# rp-schield-vias.net
KiCad netlist of a schematic drawn in EAGLE
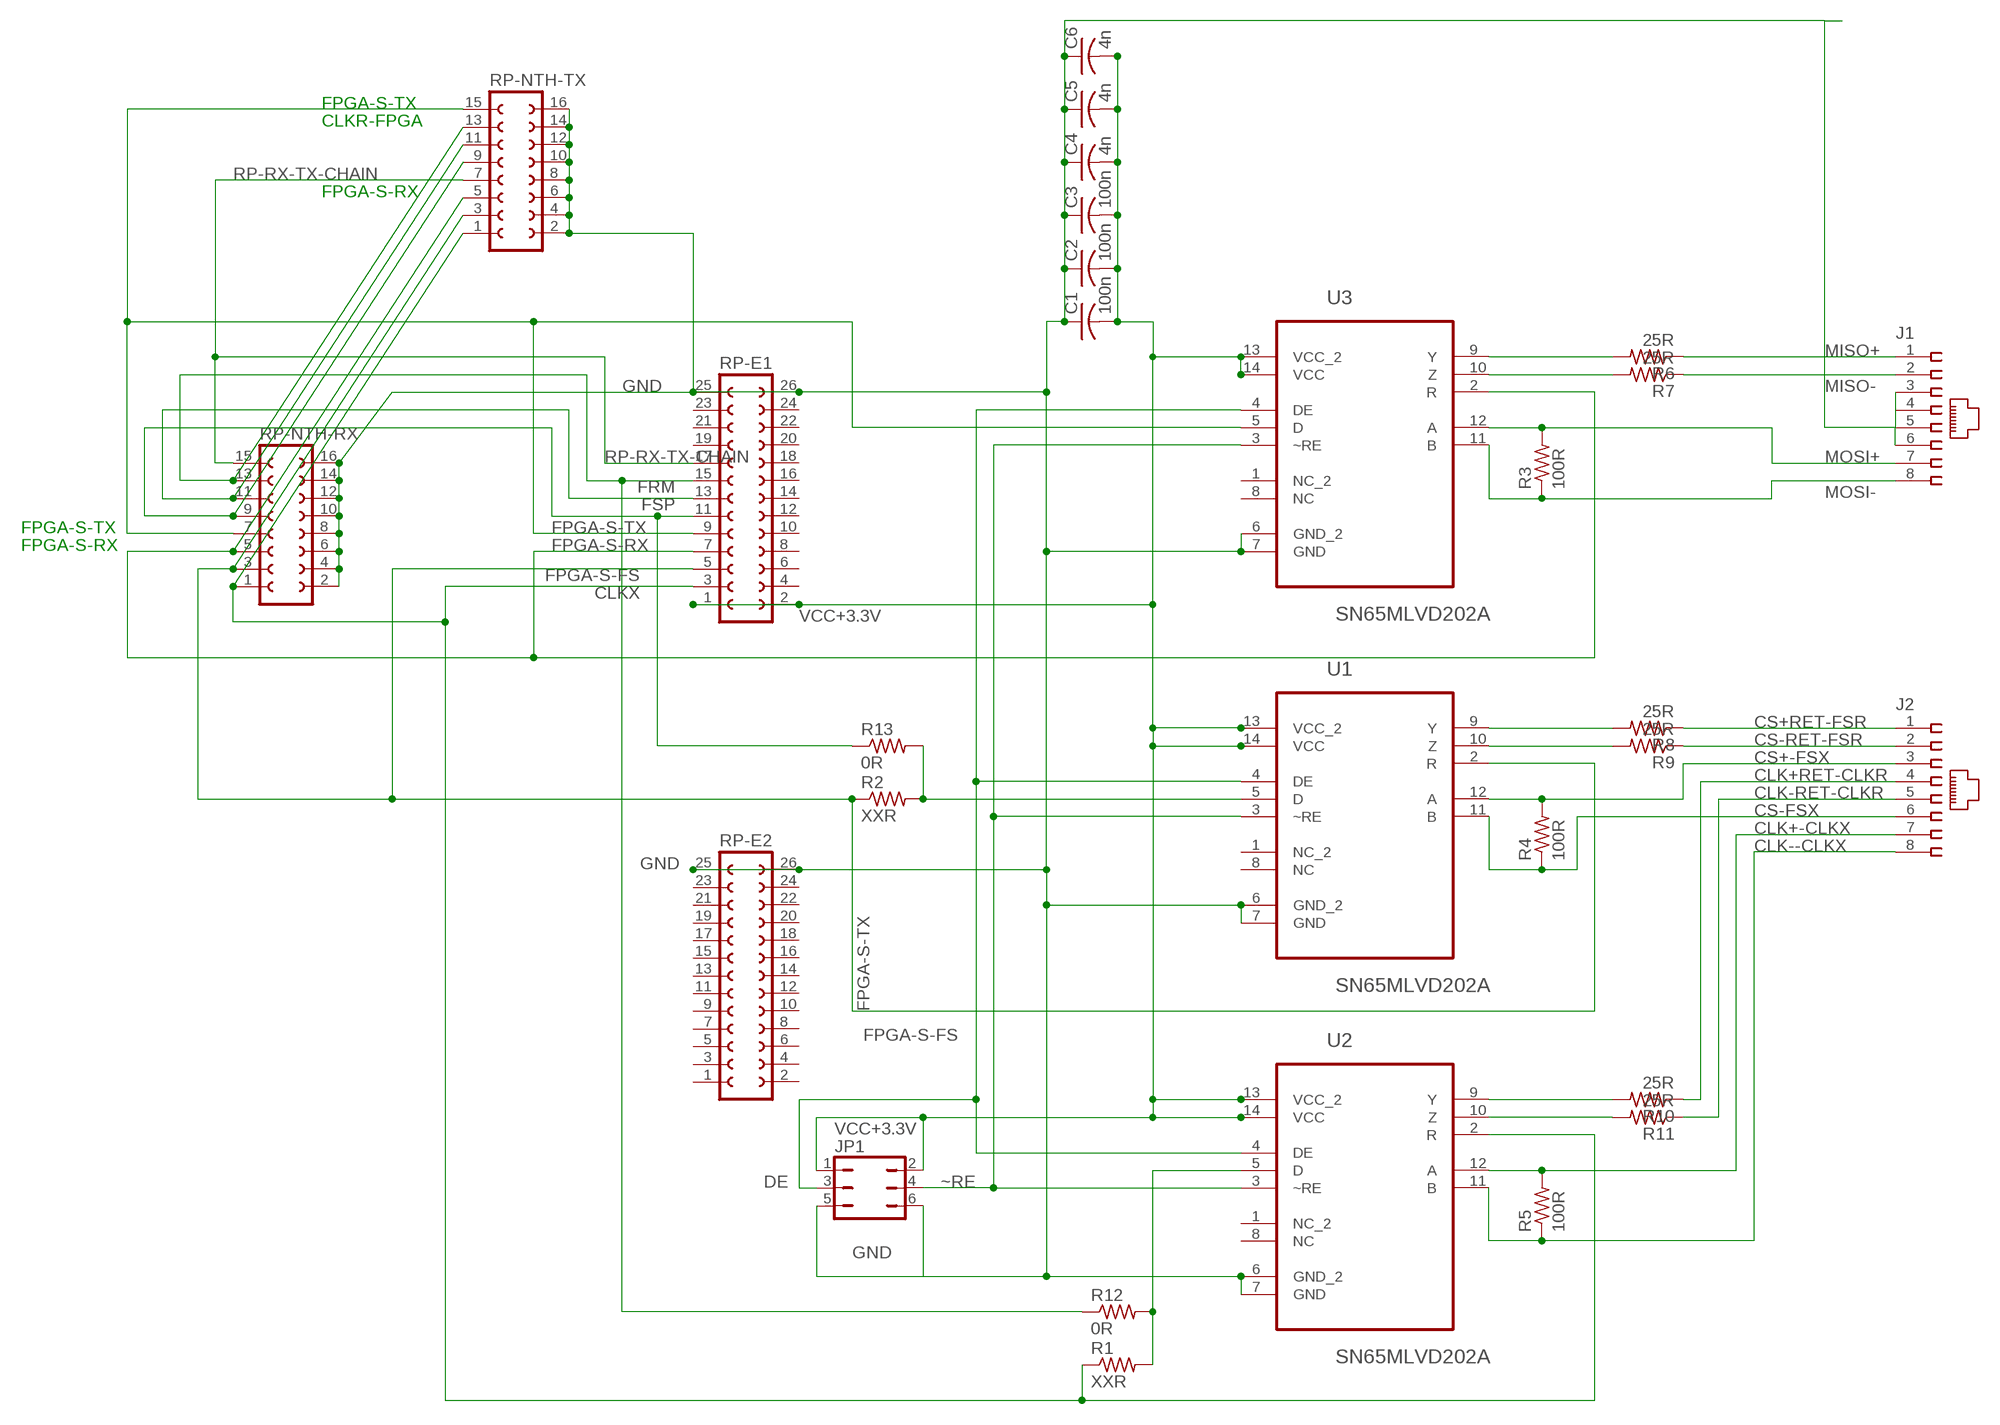
[diagram p0: schematic, sheet 1]

(export (version "E")
  (design (tool "Eeschema 10.0.6"))
  (components
    (comp (ref "C1")
      (value "100n")
      (footprint "eagle-import:C0805")
      (libsource (lib "eagle-import") (part "C-USC0805"))
    )
    (comp (ref "C2")
      (value "100n")
      (footprint "eagle-import:C0805")
      (libsource (lib "eagle-import") (part "C-USC0805"))
    )
    (comp (ref "C3")
      (value "100n")
      (footprint "eagle-import:C0805")
      (libsource (lib "eagle-import") (part "C-USC0805"))
    )
    (comp (ref "C4")
      (value "4n")
      (footprint "eagle-import:C0805")
      (libsource (lib "eagle-import") (part "C-USC0805"))
    )
    (comp (ref "C5")
      (value "4n")
      (footprint "eagle-import:C0805")
      (libsource (lib "eagle-import") (part "C-USC0805"))
    )
    (comp (ref "C6")
      (value "4n")
      (footprint "eagle-import:C0805")
      (libsource (lib "eagle-import") (part "C-USC0805"))
    )
    (comp (ref "J1")
      (value "557785-1-SHIELD")
      (footprint "eagle-import:557785-1")
      (libsource (lib "eagle-import") (part "557785-1-SHIELD"))
    )
    (comp (ref "J2")
      (value "557785-1-SHIELD")
      (footprint "eagle-import:557785-1")
      (libsource (lib "eagle-import") (part "557785-1-SHIELD"))
    )
    (comp (ref "JP1")
      (value "JP3Q")
      (footprint "eagle-import:JP3Q")
      (libsource (lib "eagle-import") (part "JP3Q"))
    )
    (comp (ref "R1")
      (value "XXR")
      (footprint "eagle-import:M1206")
      (libsource (lib "eagle-import") (part "R-US_M1206"))
    )
    (comp (ref "R2")
      (value "XXR")
      (footprint "eagle-import:M1206")
      (libsource (lib "eagle-import") (part "R-US_M1206"))
    )
    (comp (ref "R3")
      (value "100R")
      (footprint "eagle-import:R0402")
      (libsource (lib "eagle-import") (part "R-US_R0402"))
    )
    (comp (ref "R4")
      (value "100R")
      (footprint "eagle-import:R0402")
      (libsource (lib "eagle-import") (part "R-US_R0402"))
    )
    (comp (ref "R5")
      (value "100R")
      (footprint "eagle-import:R0402")
      (libsource (lib "eagle-import") (part "R-US_R0402"))
    )
    (comp (ref "R6")
      (value "25R")
      (footprint "eagle-import:R0402")
      (libsource (lib "eagle-import") (part "R-US_R0402"))
    )
    (comp (ref "R7")
      (value "25R")
      (footprint "eagle-import:R0402")
      (libsource (lib "eagle-import") (part "R-US_R0402"))
    )
    (comp (ref "R8")
      (value "25R")
      (footprint "eagle-import:R0402")
      (libsource (lib "eagle-import") (part "R-US_R0402"))
    )
    (comp (ref "R9")
      (value "25R")
      (footprint "eagle-import:R0402")
      (libsource (lib "eagle-import") (part "R-US_R0402"))
    )
    (comp (ref "R10")
      (value "25R")
      (footprint "eagle-import:R0402")
      (libsource (lib "eagle-import") (part "R-US_R0402"))
    )
    (comp (ref "R11")
      (value "25R")
      (footprint "eagle-import:R0402")
      (libsource (lib "eagle-import") (part "R-US_R0402"))
    )
    (comp (ref "R12")
      (value "0R")
      (footprint "eagle-import:M1206")
      (libsource (lib "eagle-import") (part "R-US_M1206"))
    )
    (comp (ref "R13")
      (value "0R")
      (footprint "eagle-import:M1206")
      (libsource (lib "eagle-import") (part "R-US_M1206"))
    )
    (comp (ref "RP-E1")
      (value "FE13-2")
      (footprint "eagle-import:FE13-2")
      (libsource (lib "eagle-import") (part "FE13-2"))
    )
    (comp (ref "RP-E2")
      (value "FE13-2")
      (footprint "eagle-import:FE13-2")
      (libsource (lib "eagle-import") (part "FE13-2"))
    )
    (comp (ref "RP-NTH-RX")
      (value "FE08-2")
      (footprint "eagle-import:FE08-2")
      (libsource (lib "eagle-import") (part "FE08-2"))
    )
    (comp (ref "RP-NTH-TX")
      (value "FE08-2")
      (footprint "eagle-import:FE08-2")
      (libsource (lib "eagle-import") (part "FE08-2"))
    )
    (comp (ref "U1")
      (value "SN65MLVD202A")
      (footprint "eagle-import:SOIC127P600X175-14N")
      (fields (field (name "MPN") "SN65MLVD205AD"))
      (libsource (lib "eagle-import") (part "SN65MLVD205AD"))
    )
    (comp (ref "U2")
      (value "SN65MLVD202A")
      (footprint "eagle-import:SOIC127P600X175-14N")
      (fields (field (name "MPN") "SN65MLVD205AD"))
      (libsource (lib "eagle-import") (part "SN65MLVD205AD"))
    )
    (comp (ref "U3")
      (value "SN65MLVD202A")
      (footprint "eagle-import:SOIC127P600X175-14N")
      (fields (field (name "MPN") "SN65MLVD205AD"))
      (libsource (lib "eagle-import") (part "SN65MLVD205AD"))
    )
  )
  (nets
    (net (code "1") (name "/CLK+-CLKX") (class "Default")
      (node (ref "J2") (pin "4") (pinfunction "4_4") (pintype "passive"))
      (node (ref "R10") (pin "1") (pinfunction "1_1") (pintype "passive"))
    )
    (net (code "2") (name "/CLK+RET-CLKR") (class "Default")
      (node (ref "J2") (pin "7") (pinfunction "7_7") (pintype "passive"))
      (node (ref "R5") (pin "2") (pinfunction "2_2") (pintype "passive"))
      (node (ref "U2") (pin "12") (pinfunction "A_12") (pintype "output"))
    )
    (net (code "3") (name "/CLK--CLKX") (class "Default")
      (node (ref "J2") (pin "5") (pinfunction "5_5") (pintype "passive"))
      (node (ref "R11") (pin "1") (pinfunction "1_1") (pintype "passive"))
    )
    (net (code "4") (name "/CLK-RET-CLKR") (class "Default")
      (node (ref "J2") (pin "8") (pinfunction "8_8") (pintype "passive"))
      (node (ref "R5") (pin "1") (pinfunction "1_1") (pintype "passive"))
      (node (ref "U2") (pin "11") (pinfunction "B_11") (pintype "output"))
    )
    (net (code "5") (name "/CLKX") (class "Default")
      (node (ref "R1") (pin "1") (pinfunction "1_1") (pintype "passive"))
      (node (ref "RP-E1") (pin "3") (pinfunction "3_3") (pintype "passive"))
      (node (ref "RP-NTH-RX") (pin "1") (pinfunction "1_1") (pintype "passive"))
      (node (ref "RP-NTH-TX") (pin "1") (pinfunction "1_1") (pintype "passive"))
      (node (ref "U2") (pin "2") (pinfunction "R_2") (pintype "output"))
    )
    (net (code "6") (name "/CS+-FSX") (class "Default")
      (node (ref "J2") (pin "3") (pinfunction "3_3") (pintype "passive"))
      (node (ref "R4") (pin "2") (pinfunction "2_2") (pintype "passive"))
      (node (ref "U1") (pin "12") (pinfunction "A_12") (pintype "output"))
    )
    (net (code "7") (name "/CS+RET-FSR") (class "Default")
      (node (ref "J2") (pin "1") (pinfunction "1_1") (pintype "passive"))
      (node (ref "R8") (pin "1") (pinfunction "1_1") (pintype "passive"))
    )
    (net (code "8") (name "/CS-FSX") (class "Default")
      (node (ref "J2") (pin "6") (pinfunction "6_6") (pintype "passive"))
      (node (ref "R4") (pin "1") (pinfunction "1_1") (pintype "passive"))
      (node (ref "U1") (pin "11") (pinfunction "B_11") (pintype "output"))
    )
    (net (code "9") (name "/CS-RET-FSR") (class "Default")
      (node (ref "J2") (pin "2") (pinfunction "2_2") (pintype "passive"))
      (node (ref "R9") (pin "1") (pinfunction "1_1") (pintype "passive"))
    )
    (net (code "10") (name "/DE") (class "Default")
      (node (ref "JP1") (pin "3") (pinfunction "3_3") (pintype "passive"))
      (node (ref "U1") (pin "4") (pinfunction "DE_4") (pintype "input"))
      (node (ref "U2") (pin "4") (pinfunction "DE_4") (pintype "input"))
      (node (ref "U3") (pin "4") (pinfunction "DE_4") (pintype "input"))
    )
    (net (code "11") (name "/FPGA-S-FS") (class "Default")
      (node (ref "R2") (pin "1") (pinfunction "1_1") (pintype "passive"))
      (node (ref "RP-E1") (pin "5") (pinfunction "5_5") (pintype "passive"))
      (node (ref "RP-NTH-RX") (pin "3") (pinfunction "3_3") (pintype "passive"))
      (node (ref "RP-NTH-TX") (pin "3") (pinfunction "3_3") (pintype "passive"))
      (node (ref "U1") (pin "2") (pinfunction "R_2") (pintype "output"))
    )
    (net (code "12") (name "/FPGA-S-RX") (class "Default")
      (node (ref "RP-E1") (pin "7") (pinfunction "7_7") (pintype "passive"))
      (node (ref "RP-NTH-RX") (pin "5") (pinfunction "5_5") (pintype "passive"))
      (node (ref "RP-NTH-TX") (pin "5") (pinfunction "5_5") (pintype "passive"))
      (node (ref "U3") (pin "2") (pinfunction "R_2") (pintype "output"))
    )
    (net (code "13") (name "/FPGA-S-TX") (class "Default")
      (node (ref "RP-E1") (pin "9") (pinfunction "9_9") (pintype "passive"))
      (node (ref "RP-NTH-RX") (pin "7") (pinfunction "7_7") (pintype "passive"))
      (node (ref "RP-NTH-TX") (pin "15") (pinfunction "15_15") (pintype "passive"))
      (node (ref "U3") (pin "5") (pinfunction "D_5") (pintype "input"))
    )
    (net (code "14") (name "/FRM") (class "Default")
      (node (ref "RP-E1") (pin "13") (pinfunction "13_13") (pintype "passive"))
      (node (ref "RP-NTH-RX") (pin "11") (pinfunction "11_11") (pintype "passive"))
      (node (ref "RP-NTH-TX") (pin "11") (pinfunction "11_11") (pintype "passive"))
    )
    (net (code "15") (name "/FSP") (class "Default")
      (node (ref "R13") (pin "1") (pinfunction "1_1") (pintype "passive"))
      (node (ref "RP-E1") (pin "11") (pinfunction "11_11") (pintype "passive"))
      (node (ref "RP-NTH-RX") (pin "9") (pinfunction "9_9") (pintype "passive"))
      (node (ref "RP-NTH-TX") (pin "9") (pinfunction "9_9") (pintype "passive"))
    )
    (net (code "16") (name "/GND") (class "Default")
      (node (ref "C1") (pin "1") (pinfunction "1_1") (pintype "passive"))
      (node (ref "C2") (pin "1") (pinfunction "1_1") (pintype "passive"))
      (node (ref "C3") (pin "1") (pinfunction "1_1") (pintype "passive"))
      (node (ref "C4") (pin "1") (pinfunction "1_1") (pintype "passive"))
      (node (ref "C5") (pin "1") (pinfunction "1_1") (pintype "passive"))
      (node (ref "C6") (pin "1") (pinfunction "1_1") (pintype "passive"))
      (node (ref "J1") (pin "3") (pinfunction "3_3") (pintype "passive"))
      (node (ref "J1") (pin "4") (pinfunction "4_4") (pintype "passive"))
      (node (ref "J1") (pin "5") (pinfunction "5_5") (pintype "passive"))
      (node (ref "J1") (pin "6") (pinfunction "6_6") (pintype "passive"))
      (node (ref "JP1") (pin "5") (pinfunction "5_5") (pintype "passive"))
      (node (ref "JP1") (pin "6") (pinfunction "6_6") (pintype "passive"))
      (node (ref "RP-E1") (pin "25") (pinfunction "25_25") (pintype "passive"))
      (node (ref "RP-E1") (pin "26") (pinfunction "26_26") (pintype "passive"))
      (node (ref "RP-E2") (pin "25") (pinfunction "25_25") (pintype "passive"))
      (node (ref "RP-E2") (pin "26") (pinfunction "26_26") (pintype "passive"))
      (node (ref "RP-NTH-RX") (pin "10") (pinfunction "10_10") (pintype "passive"))
      (node (ref "RP-NTH-RX") (pin "12") (pinfunction "12_12") (pintype "passive"))
      (node (ref "RP-NTH-RX") (pin "14") (pinfunction "14_14") (pintype "passive"))
      (node (ref "RP-NTH-RX") (pin "16") (pinfunction "16_16") (pintype "passive"))
      (node (ref "RP-NTH-RX") (pin "2") (pinfunction "2_2") (pintype "passive"))
      (node (ref "RP-NTH-RX") (pin "4") (pinfunction "4_4") (pintype "passive"))
      (node (ref "RP-NTH-RX") (pin "6") (pinfunction "6_6") (pintype "passive"))
      (node (ref "RP-NTH-RX") (pin "8") (pinfunction "8_8") (pintype "passive"))
      (node (ref "RP-NTH-TX") (pin "10") (pinfunction "10_10") (pintype "passive"))
      (node (ref "RP-NTH-TX") (pin "12") (pinfunction "12_12") (pintype "passive"))
      (node (ref "RP-NTH-TX") (pin "14") (pinfunction "14_14") (pintype "passive"))
      (node (ref "RP-NTH-TX") (pin "16") (pinfunction "16_16") (pintype "passive"))
      (node (ref "RP-NTH-TX") (pin "2") (pinfunction "2_2") (pintype "passive"))
      (node (ref "RP-NTH-TX") (pin "4") (pinfunction "4_4") (pintype "passive"))
      (node (ref "RP-NTH-TX") (pin "6") (pinfunction "6_6") (pintype "passive"))
      (node (ref "RP-NTH-TX") (pin "8") (pinfunction "8_8") (pintype "passive"))
      (node (ref "U1") (pin "6") (pinfunction "GND_2_6") (pintype "passive"))
      (node (ref "U1") (pin "7") (pinfunction "GND_7") (pintype "passive"))
      (node (ref "U2") (pin "6") (pinfunction "GND_2_6") (pintype "passive"))
      (node (ref "U2") (pin "7") (pinfunction "GND_7") (pintype "passive"))
      (node (ref "U3") (pin "6") (pinfunction "GND_2_6") (pintype "passive"))
      (node (ref "U3") (pin "7") (pinfunction "GND_7") (pintype "passive"))
    )
    (net (code "17") (name "/MISO+") (class "Default")
      (node (ref "J1") (pin "1") (pinfunction "1_1") (pintype "passive"))
      (node (ref "R6") (pin "1") (pinfunction "1_1") (pintype "passive"))
    )
    (net (code "18") (name "/MISO-") (class "Default")
      (node (ref "J1") (pin "2") (pinfunction "2_2") (pintype "passive"))
      (node (ref "R7") (pin "1") (pinfunction "1_1") (pintype "passive"))
    )
    (net (code "19") (name "/MOSI+") (class "Default")
      (node (ref "J1") (pin "7") (pinfunction "7_7") (pintype "passive"))
      (node (ref "R3") (pin "2") (pinfunction "2_2") (pintype "passive"))
      (node (ref "U3") (pin "12") (pinfunction "A_12") (pintype "output"))
    )
    (net (code "20") (name "/MOSI-") (class "Default")
      (node (ref "J1") (pin "8") (pinfunction "8_8") (pintype "passive"))
      (node (ref "R3") (pin "1") (pinfunction "1_1") (pintype "passive"))
      (node (ref "U3") (pin "11") (pinfunction "B_11") (pintype "output"))
    )
    (net (code "21") (name "/RP-RX-TX-CHAIN") (class "Default")
      (node (ref "RP-E1") (pin "17") (pinfunction "17_17") (pintype "passive"))
      (node (ref "RP-NTH-RX") (pin "15") (pinfunction "15_15") (pintype "passive"))
      (node (ref "RP-NTH-TX") (pin "7") (pinfunction "7_7") (pintype "passive"))
    )
    (net (code "22") (name "/VCC+3.3V") (class "Default")
      (node (ref "C1") (pin "2") (pinfunction "2_2") (pintype "passive"))
      (node (ref "C2") (pin "2") (pinfunction "2_2") (pintype "passive"))
      (node (ref "C3") (pin "2") (pinfunction "2_2") (pintype "passive"))
      (node (ref "C4") (pin "2") (pinfunction "2_2") (pintype "passive"))
      (node (ref "C5") (pin "2") (pinfunction "2_2") (pintype "passive"))
      (node (ref "C6") (pin "2") (pinfunction "2_2") (pintype "passive"))
      (node (ref "JP1") (pin "1") (pinfunction "1_1") (pintype "passive"))
      (node (ref "JP1") (pin "2") (pinfunction "2_2") (pintype "passive"))
      (node (ref "RP-E1") (pin "1") (pinfunction "1_1") (pintype "passive"))
      (node (ref "RP-E1") (pin "2") (pinfunction "2_2") (pintype "passive"))
      (node (ref "U1") (pin "13") (pinfunction "VCC_2_13") (pintype "power_in"))
      (node (ref "U1") (pin "14") (pinfunction "VCC_14") (pintype "power_in"))
      (node (ref "U2") (pin "13") (pinfunction "VCC_2_13") (pintype "power_in"))
      (node (ref "U2") (pin "14") (pinfunction "VCC_14") (pintype "power_in"))
      (node (ref "U3") (pin "13") (pinfunction "VCC_2_13") (pintype "power_in"))
      (node (ref "U3") (pin "14") (pinfunction "VCC_14") (pintype "power_in"))
    )
    (net (code "23") (name "/~{RE}") (class "Default")
      (node (ref "JP1") (pin "4") (pinfunction "4_4") (pintype "passive"))
      (node (ref "U1") (pin "3") (pinfunction "~{RE}_3") (pintype "input"))
      (node (ref "U2") (pin "3") (pinfunction "~{RE}_3") (pintype "input"))
      (node (ref "U3") (pin "3") (pinfunction "~{RE}_3") (pintype "input"))
    )
    (net (code "24") (name "Net-(R12-Pad1)") (class "Default")
      (node (ref "R12") (pin "1") (pinfunction "1_1") (pintype "passive"))
      (node (ref "RP-E1") (pin "15") (pinfunction "15_15") (pintype "passive"))
      (node (ref "RP-NTH-RX") (pin "13") (pinfunction "13_13") (pintype "passive"))
      (node (ref "RP-NTH-TX") (pin "13") (pinfunction "13_13") (pintype "passive"))
    )
    (net (code "25") (name "Net-(U1-D)") (class "Default")
      (node (ref "R13") (pin "2") (pinfunction "2_2") (pintype "passive"))
      (node (ref "R2") (pin "2") (pinfunction "2_2") (pintype "passive"))
      (node (ref "U1") (pin "5") (pinfunction "D_5") (pintype "input"))
    )
    (net (code "26") (name "Net-(U1-Y)") (class "Default")
      (node (ref "R8") (pin "2") (pinfunction "2_2") (pintype "passive"))
      (node (ref "U1") (pin "9") (pinfunction "Y_9") (pintype "output"))
    )
    (net (code "27") (name "Net-(U1-Z)") (class "Default")
      (node (ref "R9") (pin "2") (pinfunction "2_2") (pintype "passive"))
      (node (ref "U1") (pin "10") (pinfunction "Z_10") (pintype "output"))
    )
    (net (code "28") (name "Net-(U2-D)") (class "Default")
      (node (ref "R1") (pin "2") (pinfunction "2_2") (pintype "passive"))
      (node (ref "R12") (pin "2") (pinfunction "2_2") (pintype "passive"))
      (node (ref "U2") (pin "5") (pinfunction "D_5") (pintype "input"))
    )
    (net (code "29") (name "Net-(U2-Y)") (class "Default")
      (node (ref "R10") (pin "2") (pinfunction "2_2") (pintype "passive"))
      (node (ref "U2") (pin "9") (pinfunction "Y_9") (pintype "output"))
    )
    (net (code "30") (name "Net-(U2-Z)") (class "Default")
      (node (ref "R11") (pin "2") (pinfunction "2_2") (pintype "passive"))
      (node (ref "U2") (pin "10") (pinfunction "Z_10") (pintype "output"))
    )
    (net (code "31") (name "Net-(U3-Y)") (class "Default")
      (node (ref "R6") (pin "2") (pinfunction "2_2") (pintype "passive"))
      (node (ref "U3") (pin "9") (pinfunction "Y_9") (pintype "output"))
    )
    (net (code "32") (name "Net-(U3-Z)") (class "Default")
      (node (ref "R7") (pin "2") (pinfunction "2_2") (pintype "passive"))
      (node (ref "U3") (pin "10") (pinfunction "Z_10") (pintype "output"))
    )
    (net (code "33") (name "unconnected-(RP-E1-Pad4)") (class "Default")
      (node (ref "RP-E1") (pin "4") (pinfunction "4_4") (pintype "passive"))
    )
    (net (code "34") (name "unconnected-(RP-E1-Pad6)") (class "Default")
      (node (ref "RP-E1") (pin "6") (pinfunction "6_6") (pintype "passive"))
    )
    (net (code "35") (name "unconnected-(RP-E1-Pad8)") (class "Default")
      (node (ref "RP-E1") (pin "8") (pinfunction "8_8") (pintype "passive"))
    )
    (net (code "36") (name "unconnected-(RP-E1-Pad10)") (class "Default")
      (node (ref "RP-E1") (pin "10") (pinfunction "10_10") (pintype "passive"))
    )
    (net (code "37") (name "unconnected-(RP-E1-Pad12)") (class "Default")
      (node (ref "RP-E1") (pin "12") (pinfunction "12_12") (pintype "passive"))
    )
    (net (code "38") (name "unconnected-(RP-E1-Pad14)") (class "Default")
      (node (ref "RP-E1") (pin "14") (pinfunction "14_14") (pintype "passive"))
    )
    (net (code "39") (name "unconnected-(RP-E1-Pad16)") (class "Default")
      (node (ref "RP-E1") (pin "16") (pinfunction "16_16") (pintype "passive"))
    )
    (net (code "40") (name "unconnected-(RP-E1-Pad18)") (class "Default")
      (node (ref "RP-E1") (pin "18") (pinfunction "18_18") (pintype "passive"))
    )
    (net (code "41") (name "unconnected-(RP-E1-Pad19)") (class "Default")
      (node (ref "RP-E1") (pin "19") (pinfunction "19_19") (pintype "passive"))
    )
    (net (code "42") (name "unconnected-(RP-E1-Pad20)") (class "Default")
      (node (ref "RP-E1") (pin "20") (pinfunction "20_20") (pintype "passive"))
    )
    (net (code "43") (name "unconnected-(RP-E1-Pad21)") (class "Default")
      (node (ref "RP-E1") (pin "21") (pinfunction "21_21") (pintype "passive"))
    )
    (net (code "44") (name "unconnected-(RP-E1-Pad22)") (class "Default")
      (node (ref "RP-E1") (pin "22") (pinfunction "22_22") (pintype "passive"))
    )
    (net (code "45") (name "unconnected-(RP-E1-Pad23)") (class "Default")
      (node (ref "RP-E1") (pin "23") (pinfunction "23_23") (pintype "passive"))
    )
    (net (code "46") (name "unconnected-(RP-E1-Pad24)") (class "Default")
      (node (ref "RP-E1") (pin "24") (pinfunction "24_24") (pintype "passive"))
    )
    (net (code "47") (name "unconnected-(RP-E2-Pad1)") (class "Default")
      (node (ref "RP-E2") (pin "1") (pinfunction "1_1") (pintype "passive"))
    )
    (net (code "48") (name "unconnected-(RP-E2-Pad2)") (class "Default")
      (node (ref "RP-E2") (pin "2") (pinfunction "2_2") (pintype "passive"))
    )
    (net (code "49") (name "unconnected-(RP-E2-Pad3)") (class "Default")
      (node (ref "RP-E2") (pin "3") (pinfunction "3_3") (pintype "passive"))
    )
    (net (code "50") (name "unconnected-(RP-E2-Pad4)") (class "Default")
      (node (ref "RP-E2") (pin "4") (pinfunction "4_4") (pintype "passive"))
    )
    (net (code "51") (name "unconnected-(RP-E2-Pad5)") (class "Default")
      (node (ref "RP-E2") (pin "5") (pinfunction "5_5") (pintype "passive"))
    )
    (net (code "52") (name "unconnected-(RP-E2-Pad6)") (class "Default")
      (node (ref "RP-E2") (pin "6") (pinfunction "6_6") (pintype "passive"))
    )
    (net (code "53") (name "unconnected-(RP-E2-Pad7)") (class "Default")
      (node (ref "RP-E2") (pin "7") (pinfunction "7_7") (pintype "passive"))
    )
    (net (code "54") (name "unconnected-(RP-E2-Pad8)") (class "Default")
      (node (ref "RP-E2") (pin "8") (pinfunction "8_8") (pintype "passive"))
    )
    (net (code "55") (name "unconnected-(RP-E2-Pad9)") (class "Default")
      (node (ref "RP-E2") (pin "9") (pinfunction "9_9") (pintype "passive"))
    )
    (net (code "56") (name "unconnected-(RP-E2-Pad10)") (class "Default")
      (node (ref "RP-E2") (pin "10") (pinfunction "10_10") (pintype "passive"))
    )
    (net (code "57") (name "unconnected-(RP-E2-Pad11)") (class "Default")
      (node (ref "RP-E2") (pin "11") (pinfunction "11_11") (pintype "passive"))
    )
    (net (code "58") (name "unconnected-(RP-E2-Pad12)") (class "Default")
      (node (ref "RP-E2") (pin "12") (pinfunction "12_12") (pintype "passive"))
    )
    (net (code "59") (name "unconnected-(RP-E2-Pad13)") (class "Default")
      (node (ref "RP-E2") (pin "13") (pinfunction "13_13") (pintype "passive"))
    )
    (net (code "60") (name "unconnected-(RP-E2-Pad14)") (class "Default")
      (node (ref "RP-E2") (pin "14") (pinfunction "14_14") (pintype "passive"))
    )
    (net (code "61") (name "unconnected-(RP-E2-Pad15)") (class "Default")
      (node (ref "RP-E2") (pin "15") (pinfunction "15_15") (pintype "passive"))
    )
    (net (code "62") (name "unconnected-(RP-E2-Pad16)") (class "Default")
      (node (ref "RP-E2") (pin "16") (pinfunction "16_16") (pintype "passive"))
    )
    (net (code "63") (name "unconnected-(RP-E2-Pad17)") (class "Default")
      (node (ref "RP-E2") (pin "17") (pinfunction "17_17") (pintype "passive"))
    )
    (net (code "64") (name "unconnected-(RP-E2-Pad18)") (class "Default")
      (node (ref "RP-E2") (pin "18") (pinfunction "18_18") (pintype "passive"))
    )
    (net (code "65") (name "unconnected-(RP-E2-Pad19)") (class "Default")
      (node (ref "RP-E2") (pin "19") (pinfunction "19_19") (pintype "passive"))
    )
    (net (code "66") (name "unconnected-(RP-E2-Pad20)") (class "Default")
      (node (ref "RP-E2") (pin "20") (pinfunction "20_20") (pintype "passive"))
    )
    (net (code "67") (name "unconnected-(RP-E2-Pad21)") (class "Default")
      (node (ref "RP-E2") (pin "21") (pinfunction "21_21") (pintype "passive"))
    )
    (net (code "68") (name "unconnected-(RP-E2-Pad22)") (class "Default")
      (node (ref "RP-E2") (pin "22") (pinfunction "22_22") (pintype "passive"))
    )
    (net (code "69") (name "unconnected-(RP-E2-Pad23)") (class "Default")
      (node (ref "RP-E2") (pin "23") (pinfunction "23_23") (pintype "passive"))
    )
    (net (code "70") (name "unconnected-(RP-E2-Pad24)") (class "Default")
      (node (ref "RP-E2") (pin "24") (pinfunction "24_24") (pintype "passive"))
    )
    (net (code "71") (name "unconnected-(U1-NC-Pad8)") (class "Default")
      (node (ref "U1") (pin "8") (pinfunction "NC_8") (pintype "no_connect"))
    )
    (net (code "72") (name "unconnected-(U1-NC_2-Pad1)") (class "Default")
      (node (ref "U1") (pin "1") (pinfunction "NC_2_1") (pintype "no_connect"))
    )
    (net (code "73") (name "unconnected-(U2-NC-Pad8)") (class "Default")
      (node (ref "U2") (pin "8") (pinfunction "NC_8") (pintype "no_connect"))
    )
    (net (code "74") (name "unconnected-(U2-NC_2-Pad1)") (class "Default")
      (node (ref "U2") (pin "1") (pinfunction "NC_2_1") (pintype "no_connect"))
    )
    (net (code "75") (name "unconnected-(U3-NC-Pad8)") (class "Default")
      (node (ref "U3") (pin "8") (pinfunction "NC_8") (pintype "no_connect"))
    )
    (net (code "76") (name "unconnected-(U3-NC_2-Pad1)") (class "Default")
      (node (ref "U3") (pin "1") (pinfunction "NC_2_1") (pintype "no_connect"))
    )
  )
)
